# xt30_gh1_25.net
KiCad netlist of a schematic drawn in EasyEDA Pro
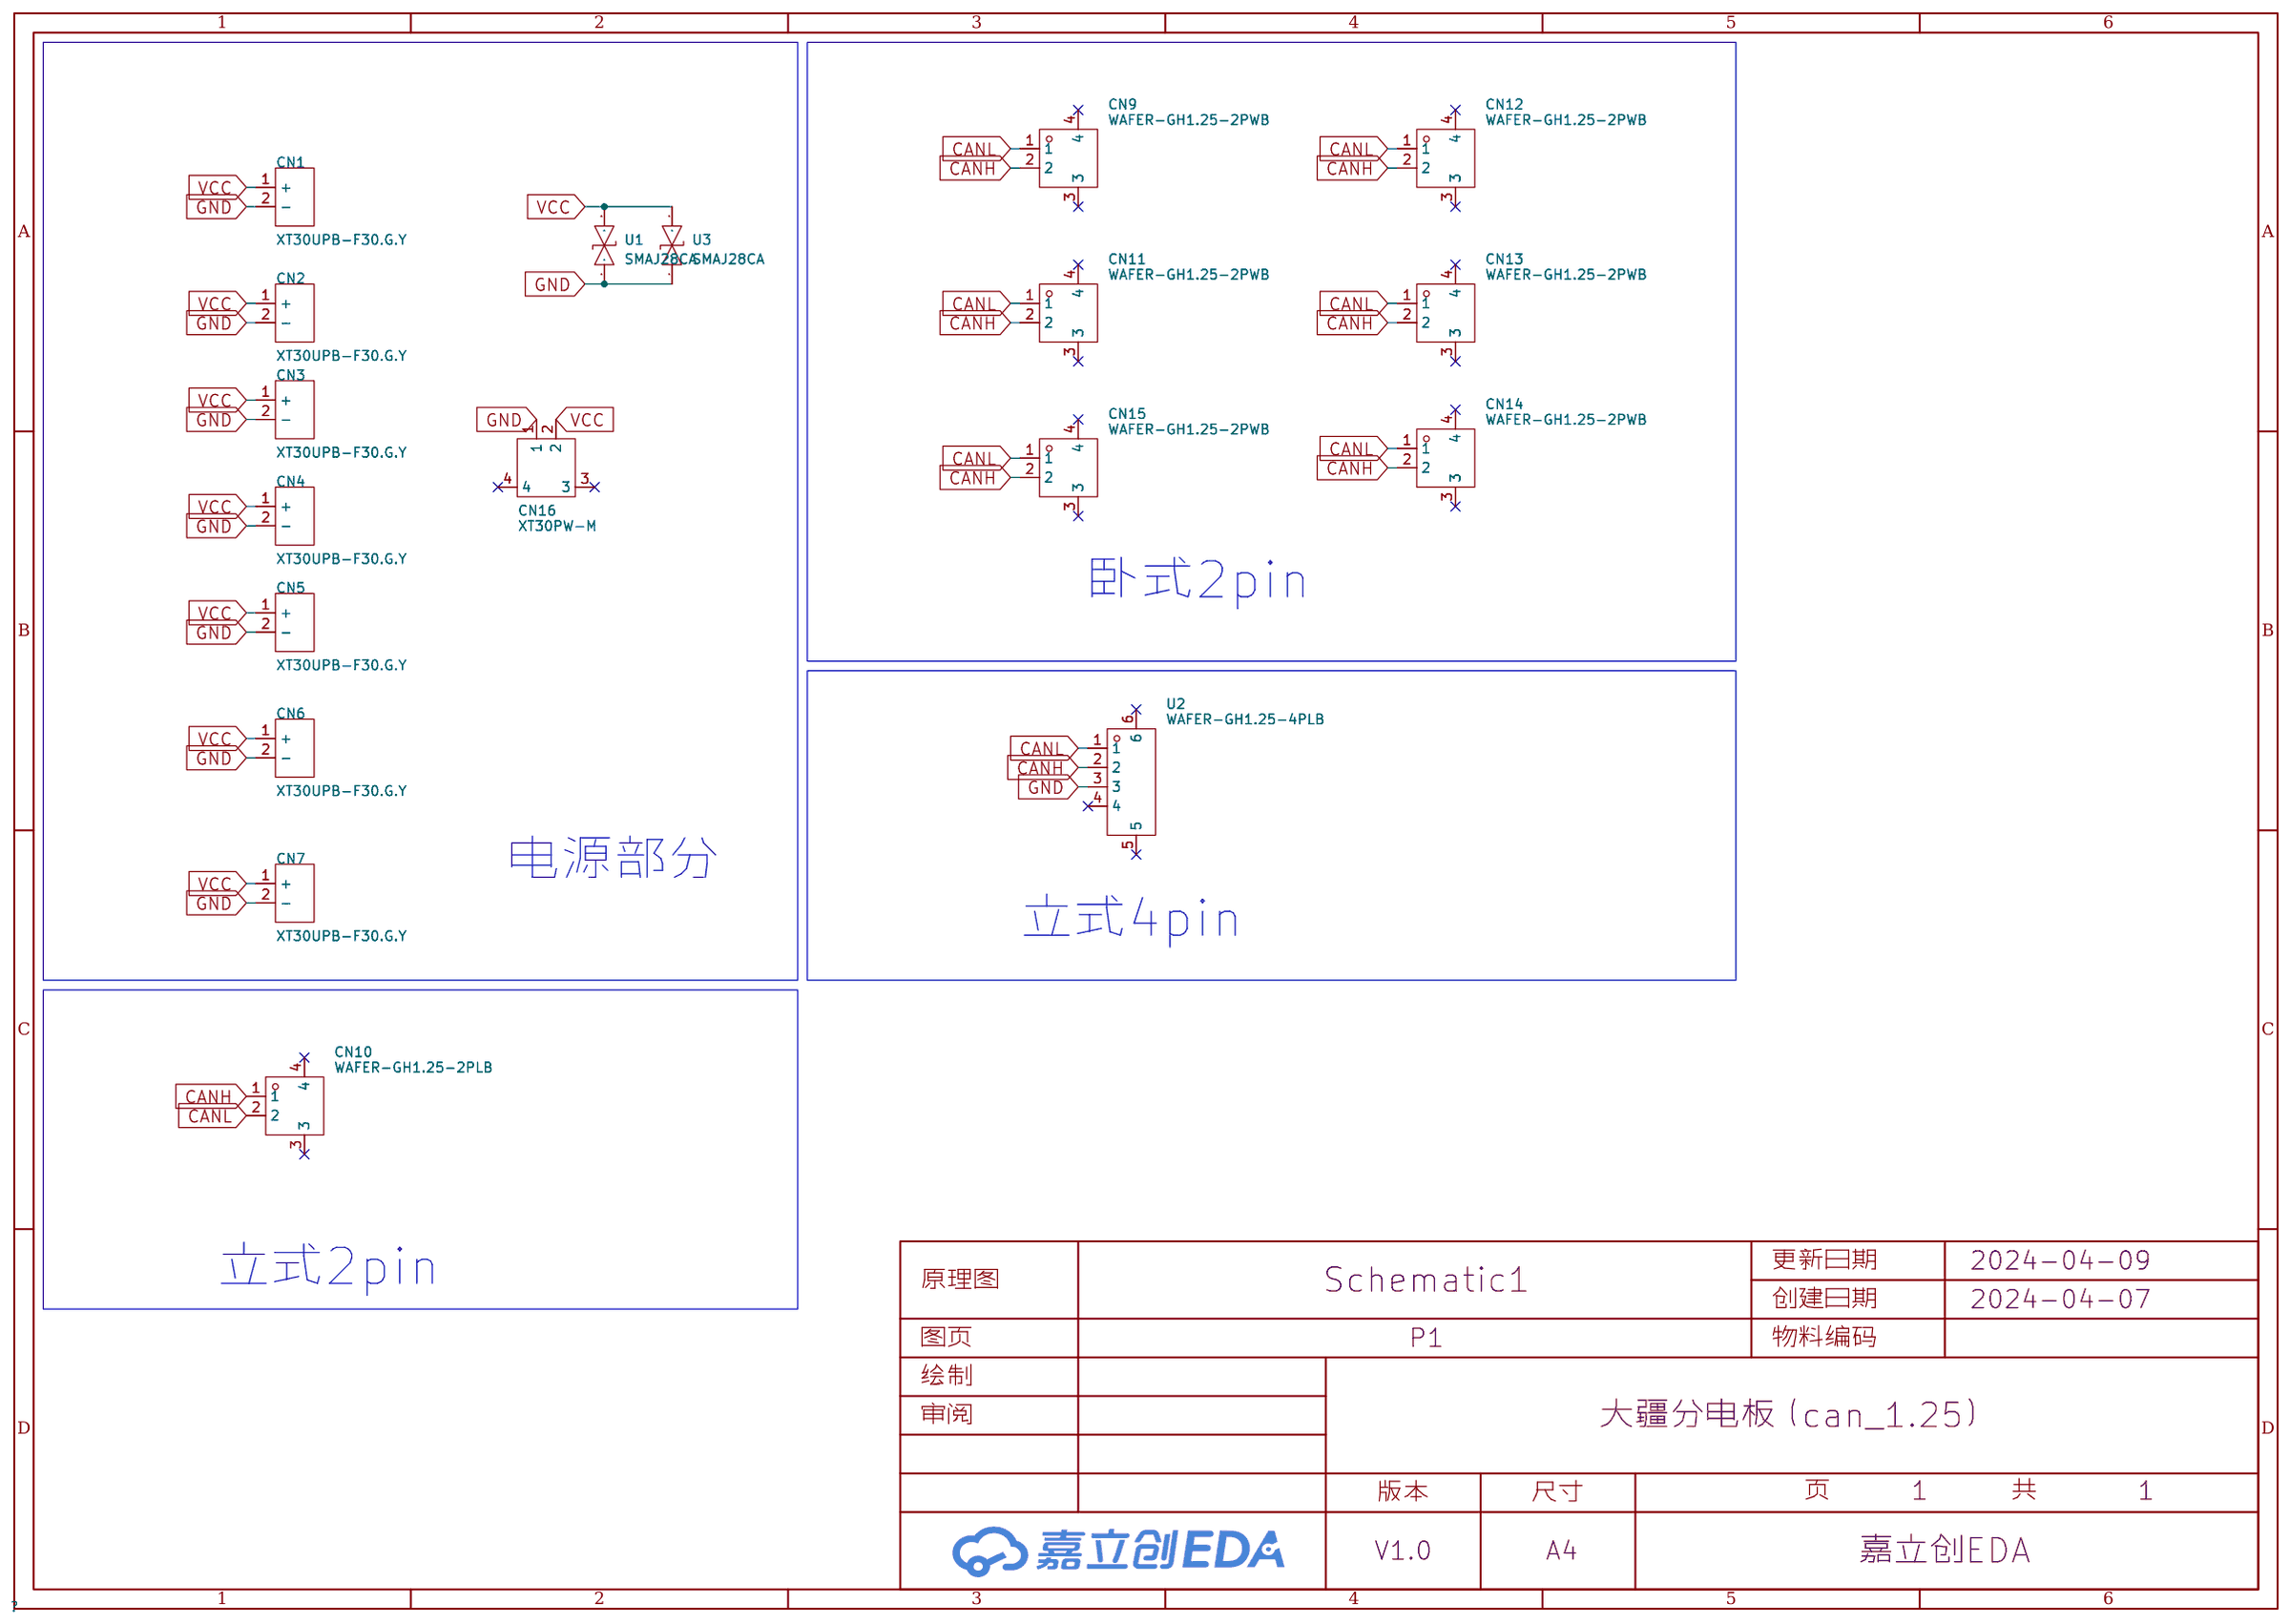
[diagram p0: schematic sheet]

(export (version "E")
  (design (tool "Eeschema 10.0.6"))
  (components
    (comp (ref "CN1")
      (value "XT30UPB-F30.G.Y")
      (footprint "easyedapro:CONN-TH_XT30UPB-F")
      (description "类别:-;类型1:-;")
      (fields (field (name "Manufacturer") "AMASS(艾迈斯)"))
      (libsource (lib "easyedapro") (part "XT30UPB-F"))
    )
    (comp (ref "CN2")
      (value "XT30UPB-F30.G.Y")
      (footprint "easyedapro:CONN-TH_XT30UPB-F")
      (description "类别:-;类型1:-;")
      (fields (field (name "Manufacturer") "AMASS(艾迈斯)"))
      (libsource (lib "easyedapro") (part "XT30UPB-F"))
    )
    (comp (ref "CN3")
      (value "XT30UPB-F30.G.Y")
      (footprint "easyedapro:CONN-TH_XT30UPB-F")
      (description "类别:-;类型1:-;")
      (fields (field (name "Manufacturer") "AMASS(艾迈斯)"))
      (libsource (lib "easyedapro") (part "XT30UPB-F"))
    )
    (comp (ref "CN4")
      (value "XT30UPB-F30.G.Y")
      (footprint "easyedapro:CONN-TH_XT30UPB-F")
      (description "类别:-;类型1:-;")
      (fields (field (name "Manufacturer") "AMASS(艾迈斯)"))
      (libsource (lib "easyedapro") (part "XT30UPB-F"))
    )
    (comp (ref "CN5")
      (value "XT30UPB-F30.G.Y")
      (footprint "easyedapro:CONN-TH_XT30UPB-F")
      (description "类别:-;类型1:-;")
      (fields (field (name "Manufacturer") "AMASS(艾迈斯)"))
      (libsource (lib "easyedapro") (part "XT30UPB-F"))
    )
    (comp (ref "CN6")
      (value "XT30UPB-F30.G.Y")
      (footprint "easyedapro:CONN-TH_XT30UPB-F")
      (description "类别:-;类型1:-;")
      (fields (field (name "Manufacturer") "AMASS(艾迈斯)"))
      (libsource (lib "easyedapro") (part "XT30UPB-F"))
    )
    (comp (ref "CN7")
      (value "XT30UPB-F30.G.Y")
      (footprint "easyedapro:CONN-TH_XT30UPB-F")
      (description "类别:-;类型1:-;")
      (fields (field (name "Manufacturer") "AMASS(艾迈斯)"))
      (libsource (lib "easyedapro") (part "XT30UPB-F"))
    )
    (comp (ref "CN9")
      (value "WAFER-GH1.25-2PWB")
      (footprint "easyedapro:CONN-TH_2P-P1.25_XUNPU_WAFER-GH1.25-2PWB")
      (description "插针结构:1x2P;间距:1.25mm;安装方式:卧贴;参考系列:GH;总PIN数:2P;排数:1;每排PIN数:2;额定电流:1A;工作温度范围:-25°C~+85°C;")
      (fields (field (name "Manufacturer") "XUNPU(讯普)"))
      (libsource (lib "easyedapro") (part "WAFER-GH1.25-2PWB"))
    )
    (comp (ref "CN10")
      (value "WAFER-GH1.25-2PLB")
      (footprint "easyedapro:CONN-TH_2P-P1.25_XUNPU_WAFER-GH1.25-2PLB")
      (description "插针结构:1x2P;间距:1.25mm;安装方式:立贴;参考系列:GH;总PIN数:2P;排数:1;每排PIN数:2;额定电流:1A;工作温度范围:-25°C~+85°C;")
      (fields (field (name "Manufacturer") "XUNPU(讯普)"))
      (libsource (lib "easyedapro") (part "WAFER-GH1.25-2PLB"))
    )
    (comp (ref "CN11")
      (value "WAFER-GH1.25-2PWB")
      (footprint "easyedapro:CONN-TH_2P-P1.25_XUNPU_WAFER-GH1.25-2PWB")
      (description "插针结构:1x2P;间距:1.25mm;安装方式:卧贴;参考系列:GH;总PIN数:2P;排数:1;每排PIN数:2;额定电流:1A;工作温度范围:-25°C~+85°C;")
      (fields (field (name "Manufacturer") "XUNPU(讯普)"))
      (libsource (lib "easyedapro") (part "WAFER-GH1.25-2PWB"))
    )
    (comp (ref "CN12")
      (value "WAFER-GH1.25-2PWB")
      (footprint "easyedapro:CONN-TH_2P-P1.25_XUNPU_WAFER-GH1.25-2PWB")
      (description "插针结构:1x2P;间距:1.25mm;安装方式:卧贴;参考系列:GH;总PIN数:2P;排数:1;每排PIN数:2;额定电流:1A;工作温度范围:-25°C~+85°C;")
      (fields (field (name "Manufacturer") "XUNPU(讯普)"))
      (libsource (lib "easyedapro") (part "WAFER-GH1.25-2PWB"))
    )
    (comp (ref "CN13")
      (value "WAFER-GH1.25-2PWB")
      (footprint "easyedapro:CONN-TH_2P-P1.25_XUNPU_WAFER-GH1.25-2PWB")
      (description "插针结构:1x2P;间距:1.25mm;安装方式:卧贴;参考系列:GH;总PIN数:2P;排数:1;每排PIN数:2;额定电流:1A;工作温度范围:-25°C~+85°C;")
      (fields (field (name "Manufacturer") "XUNPU(讯普)"))
      (libsource (lib "easyedapro") (part "WAFER-GH1.25-2PWB"))
    )
    (comp (ref "CN14")
      (value "WAFER-GH1.25-2PWB")
      (footprint "easyedapro:CONN-TH_2P-P1.25_XUNPU_WAFER-GH1.25-2PWB")
      (description "插针结构:1x2P;间距:1.25mm;安装方式:卧贴;参考系列:GH;总PIN数:2P;排数:1;每排PIN数:2;额定电流:1A;工作温度范围:-25°C~+85°C;")
      (fields (field (name "Manufacturer") "XUNPU(讯普)"))
      (libsource (lib "easyedapro") (part "WAFER-GH1.25-2PWB"))
    )
    (comp (ref "CN15")
      (value "WAFER-GH1.25-2PWB")
      (footprint "easyedapro:CONN-TH_2P-P1.25_XUNPU_WAFER-GH1.25-2PWB")
      (description "插针结构:1x2P;间距:1.25mm;安装方式:卧贴;参考系列:GH;总PIN数:2P;排数:1;每排PIN数:2;额定电流:1A;工作温度范围:-25°C~+85°C;")
      (fields (field (name "Manufacturer") "XUNPU(讯普)"))
      (libsource (lib "easyedapro") (part "WAFER-GH1.25-2PWB"))
    )
    (comp (ref "CN16")
      (value "XT30PW-M")
      (footprint "easyedapro:CONN-TH_XT30PW-M")
      (description "类别:-;类型1:-;")
      (fields (field (name "Manufacturer") "AMASS(艾迈斯)"))
      (libsource (lib "easyedapro") (part "XT30PW-M"))
    )
    (comp (ref "U1")
      (value "SMAJ28CA")
      (footprint "easyedapro:SMA_L4.3-W2.7-LS5.0-BI")
      (description "反向截止电压(Vrwm):28V;最大钳位电压:45.4V;峰值脉冲电流(Ipp)@10/1000us:8.8A;击穿电压:31.1V;")
      (fields (field (name "Manufacturer") "GOODWORK(固得沃克)"))
      (libsource (lib "easyedapro") (part "SMAJ28CA_C908827"))
    )
    (comp (ref "U2")
      (value "WAFER-GH1.25-4PLB")
      (footprint "easyedapro:CONN-SMD_4P-P1.25_XUNPU_WAFER-GH1.25-4PLB")
      (description "插针结构:1x4P;间距:1.25mm;安装方式:立贴;参考系列:GH;总PIN数:4P;排数:1;每排PIN数:4;额定电流:1A;工作温度范围:-25°C~+85°C;")
      (fields (field (name "Manufacturer") "XUNPU(讯普)"))
      (libsource (lib "easyedapro") (part "WAFER-GH1.25-4PLB"))
    )
    (comp (ref "U3")
      (value "SMAJ28CA")
      (footprint "easyedapro:SMA_L4.3-W2.7-LS5.0-BI")
      (description "反向截止电压(Vrwm):28V;最大钳位电压:45.4V;峰值脉冲电流(Ipp)@10/1000us:8.8A;击穿电压:31.1V;")
      (fields (field (name "Manufacturer") "GOODWORK(固得沃克)"))
      (libsource (lib "easyedapro") (part "SMAJ28CA_C908827"))
    )
  )
  (nets
    (net (code "1") (name "CANH") (class "Default")
      (node (ref "CN10") (pin "1") (pinfunction "1_1") (pintype "unspecified"))
      (node (ref "CN11") (pin "2") (pinfunction "2_2") (pintype "unspecified"))
      (node (ref "CN12") (pin "2") (pinfunction "2_2") (pintype "unspecified"))
      (node (ref "CN13") (pin "2") (pinfunction "2_2") (pintype "unspecified"))
      (node (ref "CN14") (pin "2") (pinfunction "2_2") (pintype "unspecified"))
      (node (ref "CN15") (pin "2") (pinfunction "2_2") (pintype "unspecified"))
      (node (ref "CN9") (pin "2") (pinfunction "2_2") (pintype "unspecified"))
      (node (ref "U2") (pin "2") (pinfunction "2_2") (pintype "unspecified"))
    )
    (net (code "2") (name "CANL") (class "Default")
      (node (ref "CN10") (pin "2") (pinfunction "2_2") (pintype "unspecified"))
      (node (ref "CN11") (pin "1") (pinfunction "1_1") (pintype "unspecified"))
      (node (ref "CN12") (pin "1") (pinfunction "1_1") (pintype "unspecified"))
      (node (ref "CN13") (pin "1") (pinfunction "1_1") (pintype "unspecified"))
      (node (ref "CN14") (pin "1") (pinfunction "1_1") (pintype "unspecified"))
      (node (ref "CN15") (pin "1") (pinfunction "1_1") (pintype "unspecified"))
      (node (ref "CN9") (pin "1") (pinfunction "1_1") (pintype "unspecified"))
      (node (ref "U2") (pin "1") (pinfunction "1_1") (pintype "unspecified"))
    )
    (net (code "3") (name "GND") (class "Default")
      (node (ref "CN1") (pin "2") (pinfunction "-_2") (pintype "unspecified"))
      (node (ref "CN16") (pin "1") (pinfunction "1_1") (pintype "unspecified"))
      (node (ref "CN2") (pin "2") (pinfunction "-_2") (pintype "unspecified"))
      (node (ref "CN3") (pin "2") (pinfunction "-_2") (pintype "unspecified"))
      (node (ref "CN4") (pin "2") (pinfunction "-_2") (pintype "unspecified"))
      (node (ref "CN5") (pin "2") (pinfunction "-_2") (pintype "unspecified"))
      (node (ref "CN6") (pin "2") (pinfunction "-_2") (pintype "unspecified"))
      (node (ref "CN7") (pin "2") (pinfunction "-_2") (pintype "unspecified"))
      (node (ref "U1") (pin "1") (pinfunction "1_1") (pintype "unspecified"))
      (node (ref "U2") (pin "3") (pinfunction "3_3") (pintype "unspecified"))
      (node (ref "U3") (pin "1") (pinfunction "1_1") (pintype "unspecified"))
    )
    (net (code "4") (name "VCC") (class "Default")
      (node (ref "CN1") (pin "1") (pinfunction "+_1") (pintype "unspecified"))
      (node (ref "CN16") (pin "2") (pinfunction "2_2") (pintype "unspecified"))
      (node (ref "CN2") (pin "1") (pinfunction "+_1") (pintype "unspecified"))
      (node (ref "CN3") (pin "1") (pinfunction "+_1") (pintype "unspecified"))
      (node (ref "CN4") (pin "1") (pinfunction "+_1") (pintype "unspecified"))
      (node (ref "CN5") (pin "1") (pinfunction "+_1") (pintype "unspecified"))
      (node (ref "CN6") (pin "1") (pinfunction "+_1") (pintype "unspecified"))
      (node (ref "CN7") (pin "1") (pinfunction "+_1") (pintype "unspecified"))
      (node (ref "U1") (pin "2") (pinfunction "2_2") (pintype "unspecified"))
      (node (ref "U3") (pin "2") (pinfunction "2_2") (pintype "unspecified"))
    )
    (net (code "5") (name "unconnected-(CN9-Pad3)") (class "Default")
      (node (ref "CN9") (pin "3") (pinfunction "3_3") (pintype "unspecified+no_connect"))
    )
    (net (code "6") (name "unconnected-(CN9-Pad4)") (class "Default")
      (node (ref "CN9") (pin "4") (pinfunction "4_4") (pintype "unspecified+no_connect"))
    )
    (net (code "7") (name "unconnected-(CN10-Pad3)") (class "Default")
      (node (ref "CN10") (pin "3") (pinfunction "3_3") (pintype "unspecified+no_connect"))
    )
    (net (code "8") (name "unconnected-(CN10-Pad4)") (class "Default")
      (node (ref "CN10") (pin "4") (pinfunction "4_4") (pintype "unspecified+no_connect"))
    )
    (net (code "9") (name "unconnected-(CN11-Pad3)") (class "Default")
      (node (ref "CN11") (pin "3") (pinfunction "3_3") (pintype "unspecified+no_connect"))
    )
    (net (code "10") (name "unconnected-(CN11-Pad4)") (class "Default")
      (node (ref "CN11") (pin "4") (pinfunction "4_4") (pintype "unspecified+no_connect"))
    )
    (net (code "11") (name "unconnected-(CN12-Pad3)") (class "Default")
      (node (ref "CN12") (pin "3") (pinfunction "3_3") (pintype "unspecified+no_connect"))
    )
    (net (code "12") (name "unconnected-(CN12-Pad4)") (class "Default")
      (node (ref "CN12") (pin "4") (pinfunction "4_4") (pintype "unspecified+no_connect"))
    )
    (net (code "13") (name "unconnected-(CN13-Pad3)") (class "Default")
      (node (ref "CN13") (pin "3") (pinfunction "3_3") (pintype "unspecified+no_connect"))
    )
    (net (code "14") (name "unconnected-(CN13-Pad4)") (class "Default")
      (node (ref "CN13") (pin "4") (pinfunction "4_4") (pintype "unspecified+no_connect"))
    )
    (net (code "15") (name "unconnected-(CN14-Pad3)") (class "Default")
      (node (ref "CN14") (pin "3") (pinfunction "3_3") (pintype "unspecified+no_connect"))
    )
    (net (code "16") (name "unconnected-(CN14-Pad4)") (class "Default")
      (node (ref "CN14") (pin "4") (pinfunction "4_4") (pintype "unspecified+no_connect"))
    )
    (net (code "17") (name "unconnected-(CN15-Pad3)") (class "Default")
      (node (ref "CN15") (pin "3") (pinfunction "3_3") (pintype "unspecified+no_connect"))
    )
    (net (code "18") (name "unconnected-(CN15-Pad4)") (class "Default")
      (node (ref "CN15") (pin "4") (pinfunction "4_4") (pintype "unspecified+no_connect"))
    )
    (net (code "19") (name "unconnected-(CN16-Pad3)") (class "Default")
      (node (ref "CN16") (pin "3") (pinfunction "3_3") (pintype "unspecified+no_connect"))
    )
    (net (code "20") (name "unconnected-(CN16-Pad4)") (class "Default")
      (node (ref "CN16") (pin "4") (pinfunction "4_4") (pintype "unspecified+no_connect"))
    )
    (net (code "21") (name "unconnected-(U2-Pad4)") (class "Default")
      (node (ref "U2") (pin "4") (pinfunction "4_4") (pintype "unspecified+no_connect"))
    )
    (net (code "22") (name "unconnected-(U2-Pad5)") (class "Default")
      (node (ref "U2") (pin "5") (pinfunction "5_5") (pintype "unspecified+no_connect"))
    )
    (net (code "23") (name "unconnected-(U2-Pad6)") (class "Default")
      (node (ref "U2") (pin "6") (pinfunction "6_6") (pintype "unspecified+no_connect"))
    )
  )
)
